# adc.net
KiCad netlist of a schematic drawn in Altium Designer
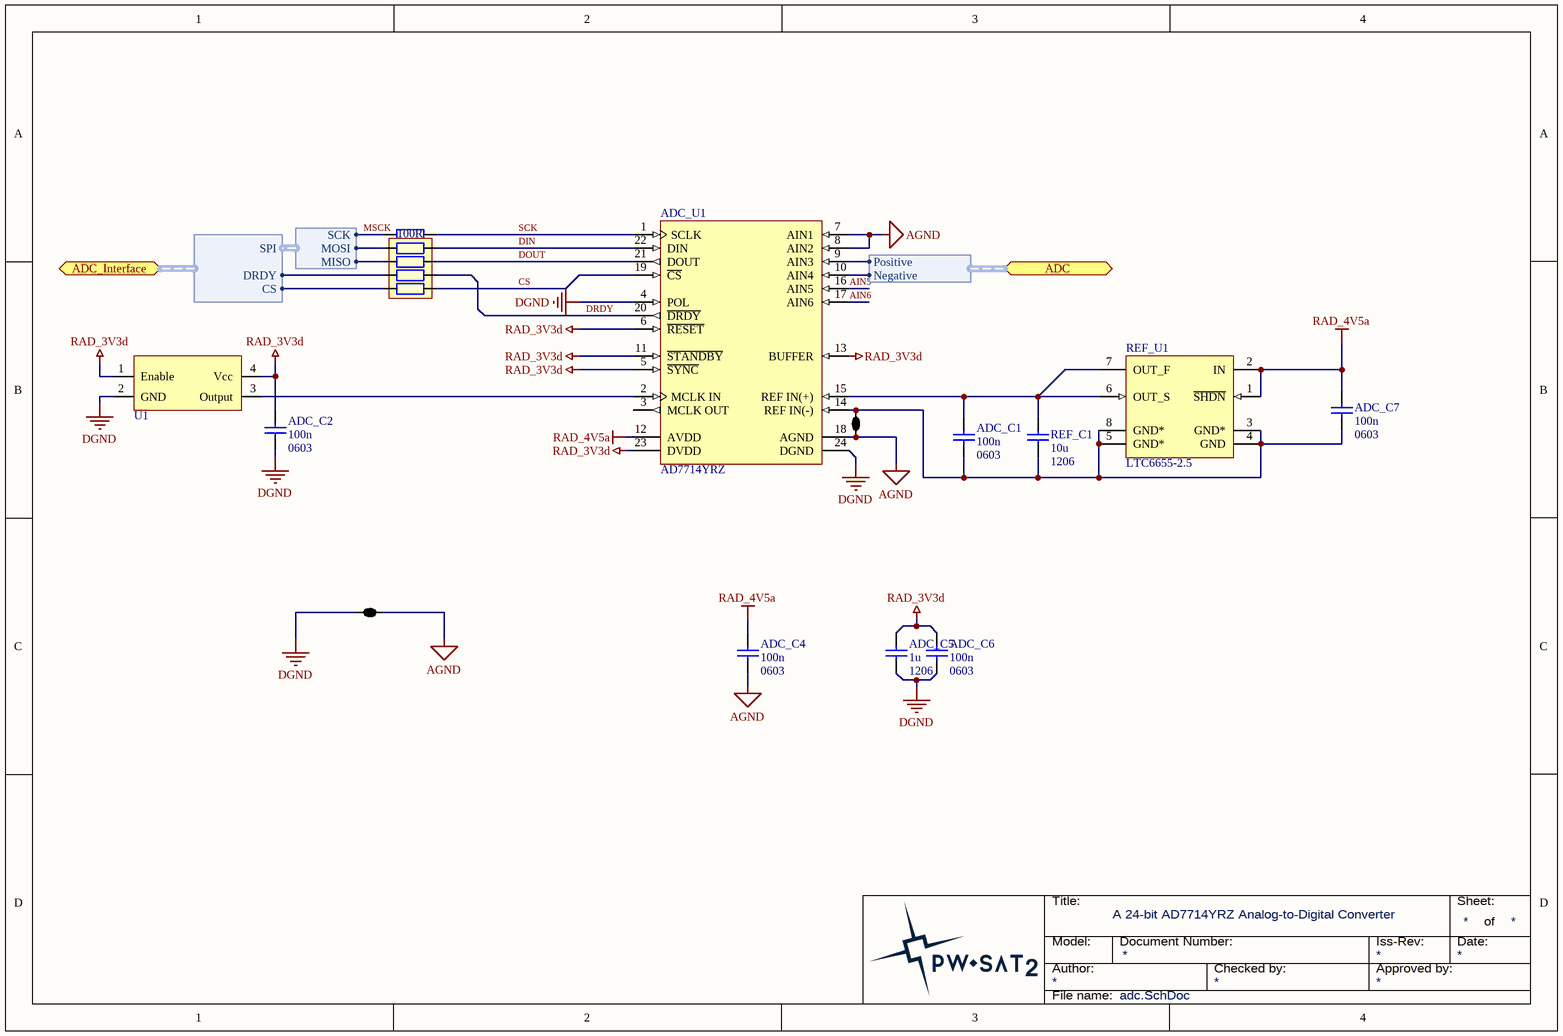
[diagram p0: adc.SchDoc]

(export (version "E")
  (design (tool "Eeschema 10.0.6"))
  (components
    (comp (ref "ADC_C1")
      (value "100n")
      (footprint "SMD_Capacitor_0603")
      (description "Cap")
      (fields (field (name "PACKAGE") "0603"))
      (libsource (lib "capacitors") (part "Cap"))
    )
    (comp (ref "ADC_C2")
      (value "100n")
      (footprint "SMD_Capacitor_0603")
      (description "Cap")
      (fields (field (name "PACKAGE") "0603"))
      (libsource (lib "capacitors") (part "Cap"))
    )
    (comp (ref "ADC_C4")
      (value "100n")
      (footprint "SMD_Capacitor_0603")
      (description "Cap")
      (fields (field (name "PACKAGE") "0603"))
      (libsource (lib "capacitors") (part "Cap"))
    )
    (comp (ref "ADC_C5")
      (value "1u")
      (footprint "SMD_Capacitor_1206")
      (description "Cap")
      (fields (field (name "PACKAGE") "1206"))
      (libsource (lib "capacitors") (part "Cap"))
    )
    (comp (ref "ADC_C6")
      (value "100n")
      (footprint "SMD_Capacitor_0603")
      (description "Cap")
      (fields (field (name "PACKAGE") "0603"))
      (libsource (lib "capacitors") (part "Cap"))
    )
    (comp (ref "ADC_C7")
      (value "100n")
      (footprint "SMD_Capacitor_0603")
      (description "Cap")
      (fields (field (name "PACKAGE") "0603"))
      (libsource (lib "capacitors") (part "Cap"))
    )
    (comp (ref "ADC_J1")
      (value "2 way net tie junction")
      (footprint "2way_LP")
      (libsource (lib "NetTieLib") (part "2way"))
    )
    (comp (ref "ADC_J2")
      (value "2 way net tie junction")
      (footprint "2way_LP")
      (libsource (lib "") (part "2way_1"))
    )
    (comp (ref "ADC_R1")
      (value "100R")
      (footprint "SMD_Resistor_0603")
      (libsource (lib "resistors") (part "Res"))
    )
    (comp (ref "ADC_R2")
      (value "YC124-JR-072K2L")
      (footprint "SMD_RESISTOR_ARRAY_YC124")
      (description "RESISTOR ARRAY, 4 x 0402")
      (libsource (lib "resistors") (part "YC124-JR-072K2L"))
    )
    (comp (ref "ADC_U1")
      (value "AD7714YRZ")
      (footprint "TSSOP-24-RU-24-N")
      (fields (field (name "GENERIC PART NUMBER") "AD7714") (field (name "MANUFACTURER") "Analog Devices"))
      (libsource (lib "microcircuits") (part "AD7714YRZ"))
    )
    (comp (ref "REF_C1")
      (value "10u")
      (footprint "SMD_Capacitor_1206")
      (description "Cap")
      (fields (field (name "PACKAGE") "1206"))
      (libsource (lib "capacitors") (part "Cap"))
    )
    (comp (ref "REF_U1")
      (value "LTC6655-2.5")
      (footprint "MSOP-8")
      (description "0.25ppm Noise, Low Drift  Precision References")
      (libsource (lib "microcircuits") (part "LTC6655-2.5"))
    )
    (comp (ref "U1")
      (value "Ceramic Crystal")
      (footprint "2.0 x 2.5 mm")
      (description "Ceramic Crystal 1 MHz, A-Grade 25 ppm/deg")
      (libsource (lib "crystal") (part "ISM95-3351AH-1.0000"))
    )
  )
  (nets
    (net (code "6") (name "/AIN5") (class "Default")
      (node (ref "ADC_U1") (pin "16") (pinfunction "AIN5_16") (pintype "input"))
    )
    (net (code "7") (name "/AIN6") (class "Default")
      (node (ref "ADC_U1") (pin "17") (pinfunction "AIN6_17") (pintype "input"))
    )
    (net (code "8") (name "/CS") (class "Default")
      (node (ref "ADC_R2") (pin "4") (pinfunction "4_4") (pintype "passive"))
      (node (ref "ADC_U1") (pin "19") (pinfunction "~{CS}_19") (pintype "input"))
    )
    (net (code "9") (name "/DIN") (class "Default")
      (node (ref "ADC_R2") (pin "1") (pinfunction "1_1") (pintype "passive"))
      (node (ref "ADC_U1") (pin "22") (pinfunction "DIN_22") (pintype "input"))
    )
    (net (code "10") (name "/DOUT") (class "Default")
      (node (ref "ADC_R2") (pin "2") (pinfunction "2_2") (pintype "passive"))
      (node (ref "ADC_U1") (pin "21") (pinfunction "DOUT_21") (pintype "output"))
    )
    (net (code "11") (name "/DRDY") (class "Default")
      (node (ref "ADC_R2") (pin "3") (pinfunction "3_3") (pintype "passive"))
      (node (ref "ADC_U1") (pin "20") (pinfunction "~{DRDY}_20") (pintype "output"))
    )
    (net (code "12") (name "/MISO") (class "Default")
      (node (ref "ADC_R2") (pin "7") (pinfunction "7_7") (pintype "passive"))
    )
    (net (code "13") (name "/MOSI") (class "Default")
      (node (ref "ADC_R2") (pin "8") (pinfunction "8_8") (pintype "passive"))
    )
    (net (code "14") (name "/MSCK") (class "Default")
      (node (ref "ADC_R1") (pin "1") (pinfunction "1_1") (pintype "passive"))
    )
    (net (code "15") (name "/Negative") (class "Default")
      (node (ref "ADC_U1") (pin "10") (pinfunction "AIN4_10") (pintype "input"))
    )
    (net (code "16") (name "/Positive") (class "Default")
      (node (ref "ADC_U1") (pin "9") (pinfunction "AIN3_9") (pintype "input"))
    )
    (net (code "17") (name "/SCK") (class "Default")
      (node (ref "ADC_R1") (pin "2") (pinfunction "2_2") (pintype "passive"))
      (node (ref "ADC_U1") (pin "1") (pinfunction "SCLK_1") (pintype "input"))
    )
    (net (code "20") (name "AGND") (class "Default")
      (node (ref "ADC_C4") (pin "2") (pinfunction "2_2") (pintype "passive"))
      (node (ref "ADC_J1") (pin "1") (pinfunction "1_1") (pintype "passive"))
      (node (ref "ADC_J2") (pin "1") (pinfunction "1_1") (pintype "passive"))
      (node (ref "ADC_U1") (pin "18") (pinfunction "AGND_18") (pintype "power_in"))
      (node (ref "ADC_U1") (pin "7") (pinfunction "AIN1_7") (pintype "input"))
      (node (ref "ADC_U1") (pin "8") (pinfunction "AIN2_8") (pintype "input"))
    )
    (net (code "21") (name "DGND") (class "Default")
      (node (ref "ADC_C2") (pin "2") (pinfunction "2_2") (pintype "passive"))
      (node (ref "ADC_C5") (pin "2") (pinfunction "2_2") (pintype "passive"))
      (node (ref "ADC_C6") (pin "2") (pinfunction "2_2") (pintype "passive"))
      (node (ref "ADC_J1") (pin "2") (pinfunction "2_2") (pintype "passive"))
      (node (ref "ADC_U1") (pin "24") (pinfunction "DGND_24") (pintype "power_in"))
      (node (ref "ADC_U1") (pin "4") (pinfunction "POL_4") (pintype "input"))
      (node (ref "U1") (pin "2") (pinfunction "GND_2") (pintype "passive"))
    )
    (net (code "22") (name "Net-(ADC_U1-MCLK_IN)") (class "Default")
      (node (ref "ADC_U1") (pin "2") (pinfunction "MCLK_IN_2") (pintype "input"))
      (node (ref "U1") (pin "3") (pinfunction "Output_3") (pintype "passive"))
    )
    (net (code "23") (name "Net-(ADC_U1-REF_IN(+))") (class "Default")
      (node (ref "ADC_C1") (pin "1") (pinfunction "1_1") (pintype "passive"))
      (node (ref "ADC_U1") (pin "15") (pinfunction "REF_IN(+)_15") (pintype "input"))
      (node (ref "REF_C1") (pin "1") (pinfunction "1_1") (pintype "passive"))
      (node (ref "REF_U1") (pin "6") (pinfunction "OUT_S_6") (pintype "input"))
      (node (ref "REF_U1") (pin "7") (pinfunction "OUT_F_7") (pintype "power_in"))
    )
    (net (code "24") (name "Net-(ADC_U1-REF_IN(-))") (class "Default")
      (node (ref "ADC_C1") (pin "2") (pinfunction "2_2") (pintype "passive"))
      (node (ref "ADC_C7") (pin "2") (pinfunction "2_2") (pintype "passive"))
      (node (ref "ADC_J2") (pin "2") (pinfunction "2_2") (pintype "passive"))
      (node (ref "ADC_U1") (pin "14") (pinfunction "REF_IN(-)_14") (pintype "input"))
      (node (ref "REF_C1") (pin "2") (pinfunction "2_2") (pintype "passive"))
      (node (ref "REF_U1") (pin "3") (pinfunction "GND*_3") (pintype "power_in"))
      (node (ref "REF_U1") (pin "4") (pinfunction "GND_4") (pintype "power_in"))
      (node (ref "REF_U1") (pin "5") (pinfunction "GND*_5") (pintype "power_in"))
      (node (ref "REF_U1") (pin "8") (pinfunction "GND*_8") (pintype "power_in"))
    )
    (net (code "25") (name "RAD_3V3d") (class "Default")
      (node (ref "ADC_C2") (pin "1") (pinfunction "1_1") (pintype "passive"))
      (node (ref "ADC_C5") (pin "1") (pinfunction "1_1") (pintype "passive"))
      (node (ref "ADC_C6") (pin "1") (pinfunction "1_1") (pintype "passive"))
      (node (ref "ADC_U1") (pin "11") (pinfunction "~{STANDBY}_11") (pintype "input"))
      (node (ref "ADC_U1") (pin "13") (pinfunction "BUFFER_13") (pintype "input"))
      (node (ref "ADC_U1") (pin "23") (pinfunction "DVDD_23") (pintype "power_in"))
      (node (ref "ADC_U1") (pin "5") (pinfunction "~{SYNC}_5") (pintype "input"))
      (node (ref "ADC_U1") (pin "6") (pinfunction "~{RESET}_6") (pintype "input"))
      (node (ref "U1") (pin "1") (pinfunction "Enable_1") (pintype "passive"))
      (node (ref "U1") (pin "4") (pinfunction "Vcc_4") (pintype "passive"))
    )
    (net (code "26") (name "RAD_4V5a") (class "Default")
      (node (ref "ADC_C4") (pin "1") (pinfunction "1_1") (pintype "passive"))
      (node (ref "ADC_C7") (pin "1") (pinfunction "1_1") (pintype "passive"))
      (node (ref "ADC_U1") (pin "12") (pinfunction "AVDD_12") (pintype "power_in"))
      (node (ref "REF_U1") (pin "1") (pinfunction "~{SHDN}_1") (pintype "input"))
      (node (ref "REF_U1") (pin "2") (pinfunction "IN_2") (pintype "power_in"))
    )
    (net (code "27") (name "unconnected-(ADC_R2-Pad5)") (class "Default")
      (node (ref "ADC_R2") (pin "5") (pinfunction "5_5") (pintype "passive"))
    )
    (net (code "28") (name "unconnected-(ADC_R2-Pad6)") (class "Default")
      (node (ref "ADC_R2") (pin "6") (pinfunction "6_6") (pintype "passive"))
    )
    (net (code "29") (name "unconnected-(ADC_U1-MCLK_OUT-Pad3)") (class "Default")
      (node (ref "ADC_U1") (pin "3") (pinfunction "MCLK_OUT_3") (pintype "output"))
    )
  )
)
